# LVDT_Driver.net
KiCad netlist of a schematic drawn in Altium Designer
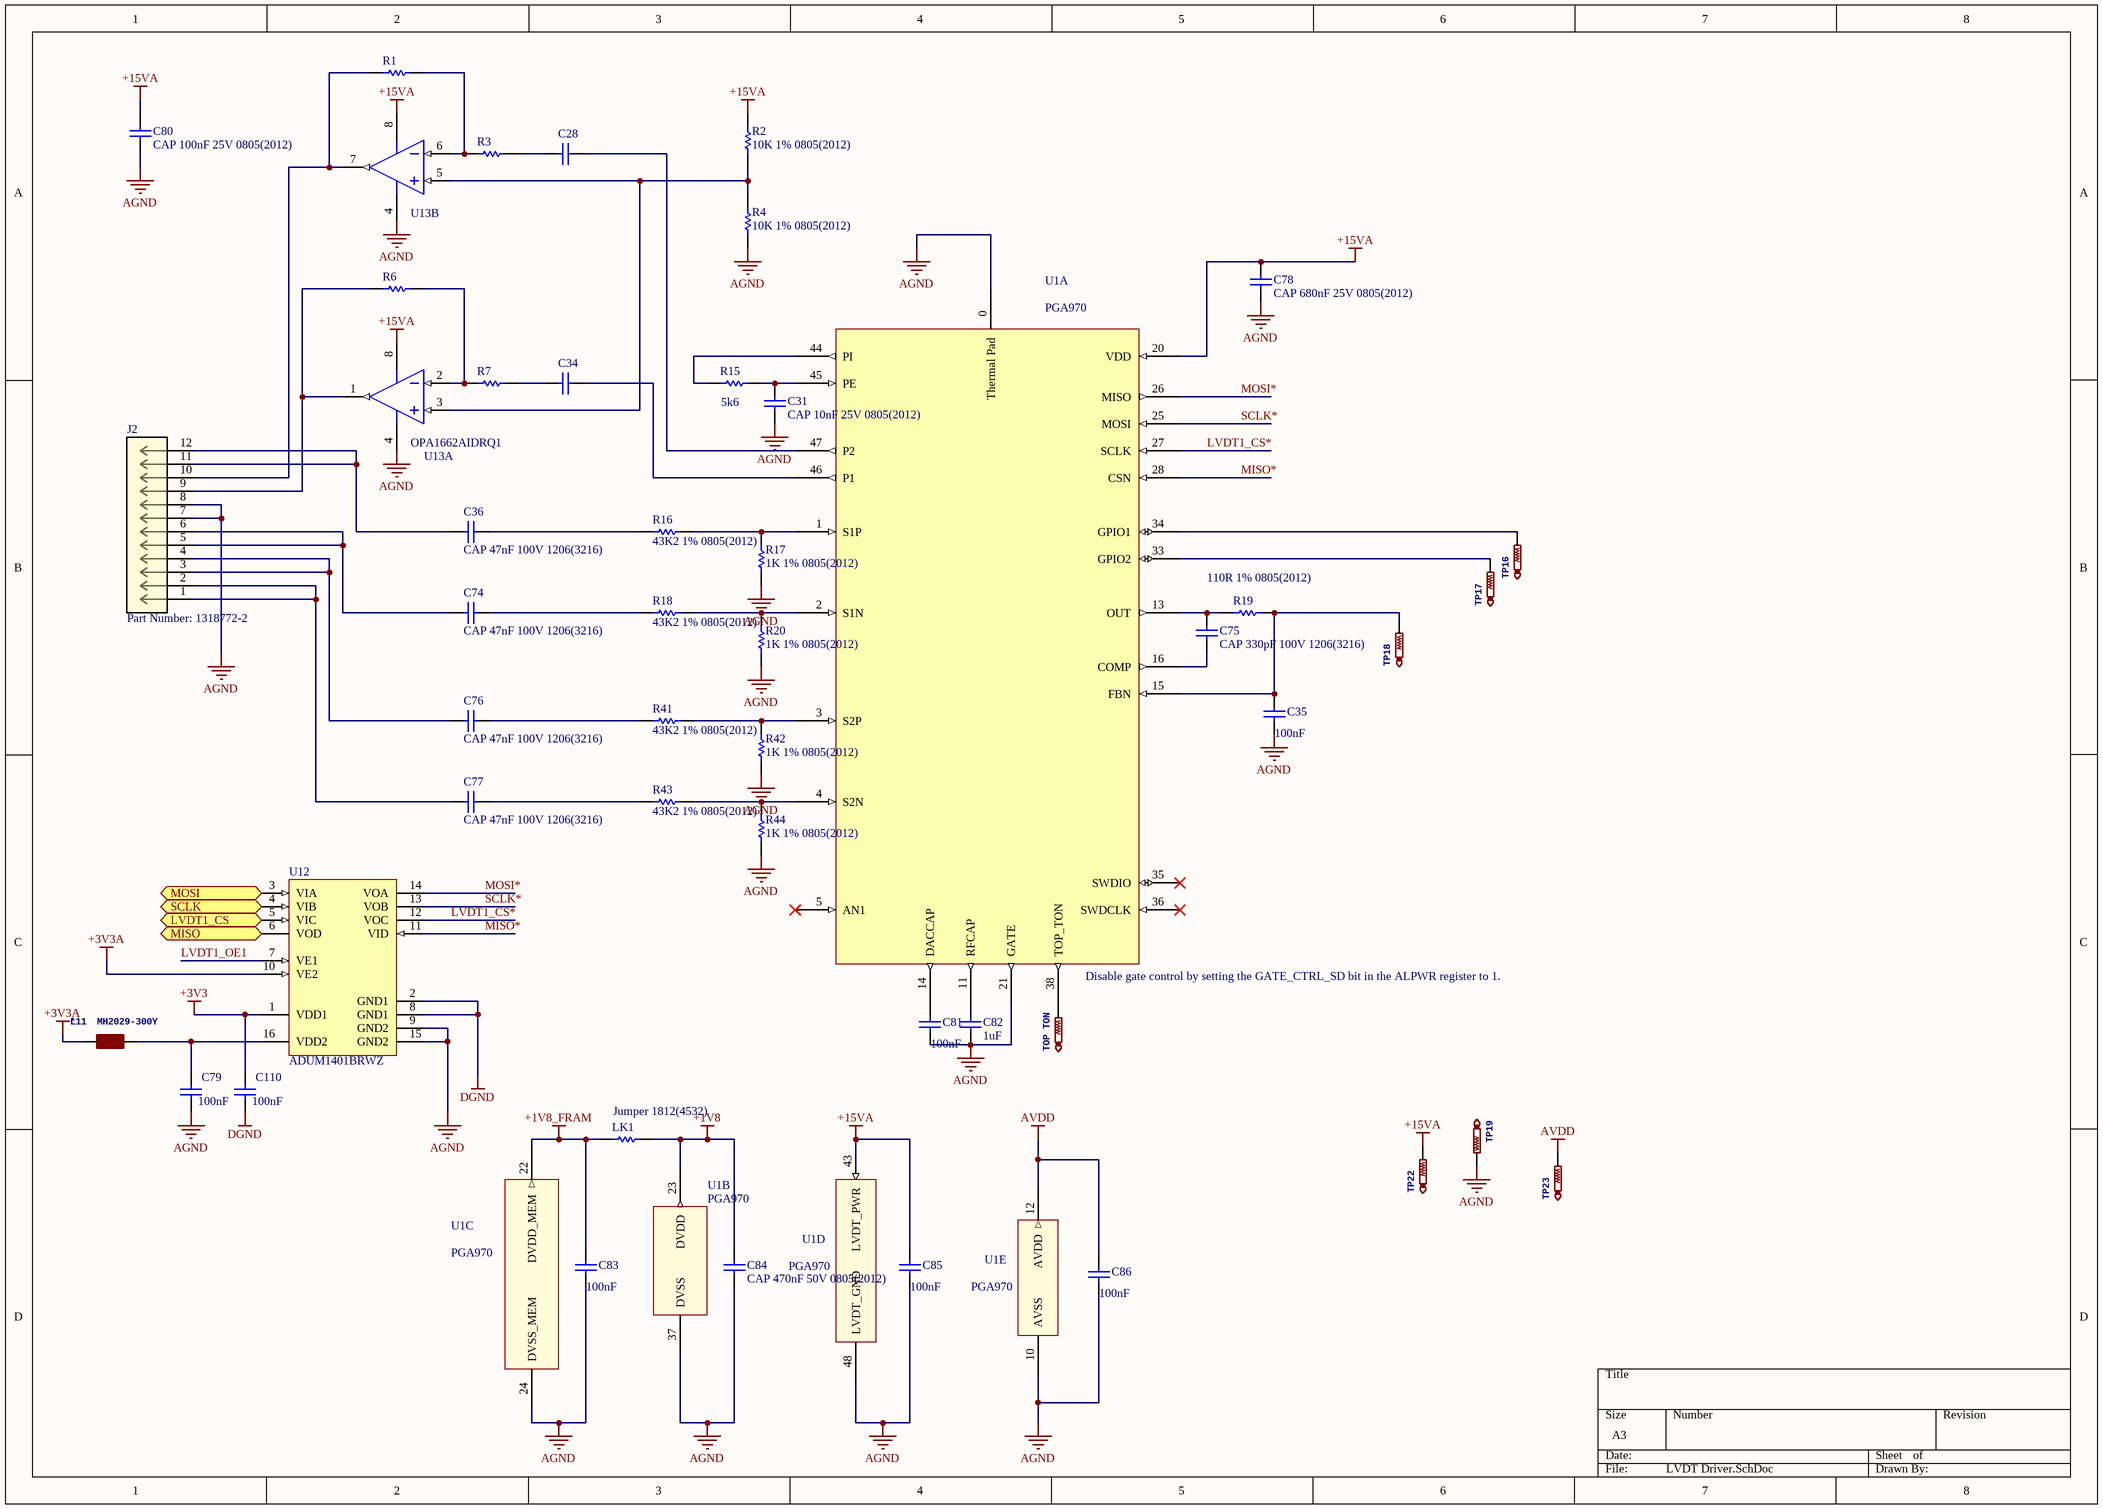
[diagram p0: LVDT Driver.SchDoc]

(export (version "E")
  (design (tool "Eeschema 10.0.6"))
  (components
    (comp (ref "C28")
      (value "C1206C474K5RACTU")
      (footprint "CAPC3216X100X50LL20T25")
      (description "Chip Capacitor, 470 nF, +/- 10%, 50 V, -55 to 125 degC, 1206 (3216 Metric), RoHS, Tape and Reel")
      (fields (field (name "MANUFACTURER") "Kemet") (field (name "TOLERANCE") "10%"))
      (libsource (lib "Altium Content Vault") (part "CAP-NP-2"))
    )
    (comp (ref "C31")
      (value "CAP 10nF 25V 0805(2012)")
      (footprint "CAPC0805(2012)75_L")
      (description "CAP 10nF 25V ±5% 0805 (2012 Metric) Thickness 0.75mm SMD")
      (fields (field (name "TOLERANCE") "Â±5%"))
      (libsource (lib "Altium Content Vault") (part "CAP"))
    )
    (comp (ref "C34")
      (value "C1206C474K5RACTU")
      (footprint "CAPC3216X100X50LL20T25")
      (description "Chip Capacitor, 470 nF, +/- 10%, 50 V, -55 to 125 degC, 1206 (3216 Metric), RoHS, Tape and Reel")
      (fields (field (name "MANUFACTURER") "Kemet") (field (name "TOLERANCE") "10%"))
      (libsource (lib "Altium Content Vault") (part "CAP-NP-2"))
    )
    (comp (ref "C35")
      (value "100nF")
      (footprint "CAPC0805(2012)75_N")
      (description "CAP 100nF 25V -20% to +80% 0805 (2012 Metric) Thickness 0.75mm SMD")
      (fields (field (name "TOLERANCE") "-20% to +80%"))
      (libsource (lib "Altium Content Vault") (part "CMP-1036-04415-1"))
    )
    (comp (ref "C36")
      (value "CAP 47nF 100V 1206(3216)")
      (footprint "CAPC1206(3216)100_L")
      (description "CAP 47nF 100V ±20% 1206 (3216 Metric) Thickness 1mm SMD")
      (fields (field (name "TOLERANCE") "Â±20%"))
      (libsource (lib "Altium Content Vault") (part "CAP"))
    )
    (comp (ref "C74")
      (value "CAP 47nF 100V 1206(3216)")
      (footprint "CAPC1206(3216)100_L")
      (description "CAP 47nF 100V ±20% 1206 (3216 Metric) Thickness 1mm SMD")
      (fields (field (name "TOLERANCE") "Â±20%"))
      (libsource (lib "Altium Content Vault") (part "CAP"))
    )
    (comp (ref "C75")
      (value "CAP 330pF 100V 1206(3216)")
      (footprint "CAPC1206(3216)170_L")
      (description "CAP 330pF 100V ±1% 1206 (3216 Metric) Thickness 1.7mm SMD")
      (fields (field (name "TOLERANCE") "Â±1%"))
      (libsource (lib "Altium Content Vault") (part "CAP"))
    )
    (comp (ref "C76")
      (value "CAP 47nF 100V 1206(3216)")
      (footprint "CAPC1206(3216)100_L")
      (description "CAP 47nF 100V ±20% 1206 (3216 Metric) Thickness 1mm SMD")
      (fields (field (name "TOLERANCE") "Â±20%"))
      (libsource (lib "Altium Content Vault") (part "CAP"))
    )
    (comp (ref "C77")
      (value "CAP 47nF 100V 1206(3216)")
      (footprint "CAPC1206(3216)100_L")
      (description "CAP 47nF 100V ±20% 1206 (3216 Metric) Thickness 1mm SMD")
      (fields (field (name "TOLERANCE") "Â±20%"))
      (libsource (lib "Altium Content Vault") (part "CAP"))
    )
    (comp (ref "C78")
      (value "CAP 680nF 25V 0805(2012)")
      (footprint "CAPC0805(2012)100_N")
      (description "CAP 680nF 25V ±10% 0805 (2012 Metric) Thickness 1mm SMD")
      (fields (field (name "TOLERANCE") "Â±10%"))
      (libsource (lib "Altium Content Vault") (part "CAP"))
    )
    (comp (ref "C79")
      (value "100nF")
      (footprint "CAPC0603(1608)100_N")
      (description "CAP 100nF 25V ±5% 0603 (1608 Metric) Thickness 1mm SMD")
      (fields (field (name "TOLERANCE") "Â±5%") (field (name "Comment") "CAP 100nF 25V 0603(1608)"))
      (libsource (lib "Altium Content Vault") (part "CMP-1035-02587-1"))
    )
    (comp (ref "C80")
      (value "CAP 100nF 25V 0805(2012)")
      (footprint "CAPC0805(2012)75_N")
      (description "CAP 100nF 25V -20% to +80% 0805 (2012 Metric) Thickness 0.75mm SMD")
      (fields (field (name "TOLERANCE") "-20% to +80%"))
      (libsource (lib "Altium Content Vault") (part "CAP"))
    )
    (comp (ref "C81")
      (value "100nF")
      (footprint "CAPC0805(2012)75_N")
      (description "CAP 100nF 25V -20% to +80% 0805 (2012 Metric) Thickness 0.75mm SMD")
      (fields (field (name "TOLERANCE") "-20% to +80%"))
      (libsource (lib "Altium Content Vault") (part "CMP-1036-04415-1"))
    )
    (comp (ref "C82")
      (value "1uF")
      (footprint "CAPC2220(5750)230_L")
      (description "CAP 4.7uF 50V ±10% 2220 (5750 Metric) Thickness 2.2mm SMD")
      (fields (field (name "TOLERANCE") "Â±10%") (field (name "Comment") "CAP 4.7uF 50V 2220(5750)"))
      (libsource (lib "Altium Content Vault") (part "CMP-1042-00755-1"))
    )
    (comp (ref "C83")
      (value "100nF")
      (footprint "CAPC0805(2012)75_N")
      (description "CAP 100nF 25V -20% to +80% 0805 (2012 Metric) Thickness 0.75mm SMD")
      (fields (field (name "TOLERANCE") "-20% to +80%"))
      (libsource (lib "Altium Content Vault") (part "CMP-1036-04415-1"))
    )
    (comp (ref "C84")
      (value "CAP 470nF 50V 0805(2012)")
      (footprint "CAPC0805(2012)145_M")
      (description "CAP 470nF 50V ±10% 0805 (2012 Metric) Thickness 1.45mm SMD")
      (fields (field (name "TOLERANCE") "Â±10%"))
      (libsource (lib "Altium Content Vault") (part "CAP"))
    )
    (comp (ref "C85")
      (value "100nF")
      (footprint "CAPC0805(2012)75_N")
      (description "CAP 100nF 25V -20% to +80% 0805 (2012 Metric) Thickness 0.75mm SMD")
      (fields (field (name "TOLERANCE") "-20% to +80%"))
      (libsource (lib "Altium Content Vault") (part "CMP-1036-04415-1"))
    )
    (comp (ref "C86")
      (value "100nF")
      (footprint "CAPC0805(2012)75_N")
      (description "CAP 100nF 25V -20% to +80% 0805 (2012 Metric) Thickness 0.75mm SMD")
      (fields (field (name "TOLERANCE") "-20% to +80%"))
      (libsource (lib "Altium Content Vault") (part "CMP-1036-04415-1"))
    )
    (comp (ref "C110")
      (value "100nF")
      (footprint "CAPC0603(1608)100_N")
      (description "CAP 100nF 25V ±5% 0603 (1608 Metric) Thickness 1mm SMD")
      (fields (field (name "TOLERANCE") "Â±5%") (field (name "Comment") "CAP 100nF 25V 0603(1608)"))
      (libsource (lib "Altium Content Vault") (part "CMP-1035-02587-1"))
    )
    (comp (ref "J2")
      (value "Part Number: 1318772-2")
      (footprint "CONN12_1318772")
      (description "025 CAP HSG ASSY 12P")
      (fields
        (field (name "MANUFACTURER_PART_NUMBER") "1318772-2")
        (field (name "COPYRIGHT") "Copyright (C) 2016 Accelerated Designs. All rights reserved")
      )
      (libsource (lib "2019-12-12_01-42-35") (part "1318772-2"))
    )
    (comp (ref "L11")
      (value "MH2029-300Y")
      (footprint "0805")
      (fields (field (name "NAME") "*"))
      (libsource (lib "wuerth-elektronik") (part "WE-CBF_0805"))
    )
    (comp (ref "LK1")
      (value "Jumper 1812(4532)")
      (footprint "RESC1812(4532)_M")
      (description "Jumper 1812 (4532 Metric)")
      (fields (field (name "TOLERANCE") "None"))
      (libsource (lib "Altium Content Vault") (part "RES"))
    )
    (comp (ref "R1")
      (value "510K 1% 0805(2012)")
      (footprint "RESC0805(2012)_L")
      (description "510K 0.125W 1% 0805 (2012 Metric)  SMD")
      (fields (field (name "POWER") "0.125 W") (field (name "TOLERANCE") "1 %"))
      (libsource (lib "Altium Content Vault") (part "RES"))
    )
    (comp (ref "R2")
      (value "10K 1% 0805(2012)")
      (footprint "RESC0805(2012)_M")
      (description "10K 0.125W 1% 0805 (2012 Metric)  SMD")
      (fields (field (name "TOLERANCE") "1 %") (field (name "POWER") "0.125 W"))
      (libsource (lib "Altium Content Vault") (part "RES"))
    )
    (comp (ref "R3")
      (value "31K6 1% 0805(2012)")
      (footprint "RESC0805(2012)_N")
      (description "31K6 0.125W 1% 0805 (2012 Metric)  SMD")
      (fields (field (name "TOLERANCE") "1 %") (field (name "POWER") "0.125 W"))
      (libsource (lib "Altium Content Vault") (part "RES"))
    )
    (comp (ref "R4")
      (value "10K 1% 0805(2012)")
      (footprint "RESC0805(2012)_M")
      (description "10K 0.125W 1% 0805 (2012 Metric)  SMD")
      (fields (field (name "TOLERANCE") "1 %") (field (name "POWER") "0.125 W"))
      (libsource (lib "Altium Content Vault") (part "RES"))
    )
    (comp (ref "R6")
      (value "510K 1% 0805(2012)")
      (footprint "RESC0805(2012)_L")
      (description "510K 0.125W 1% 0805 (2012 Metric)  SMD")
      (fields (field (name "POWER") "0.125 W") (field (name "TOLERANCE") "1 %"))
      (libsource (lib "Altium Content Vault") (part "RES"))
    )
    (comp (ref "R7")
      (value "31K6 1% 0805(2012)")
      (footprint "RESC0805(2012)_N")
      (description "31K6 0.125W 1% 0805 (2012 Metric)  SMD")
      (fields (field (name "TOLERANCE") "1 %") (field (name "POWER") "0.125 W"))
      (libsource (lib "Altium Content Vault") (part "RES"))
    )
    (comp (ref "R15")
      (value "5k6")
      (footprint "RESC0805(2012)_L")
      (description "5K6 0.125W 1% 0805 (2012 Metric)  SMD")
      (fields (field (name "POWER") "0.125 W") (field (name "TOLERANCE") "1 %"))
      (libsource (lib "Altium Content Vault") (part "CMP-1013-00595-1"))
    )
    (comp (ref "R16")
      (value "43K2 1% 0805(2012)")
      (footprint "RESC0805(2012)_L")
      (description "43K2 0.125W 1% 0805 (2012 Metric)  SMD")
      (fields (field (name "POWER") "0.125 W") (field (name "TOLERANCE") "1 %"))
      (libsource (lib "Altium Content Vault") (part "RES"))
    )
    (comp (ref "R17")
      (value "1K 1% 0805(2012)")
      (footprint "RESC0805(2012)_M")
      (description "1K 0.125W 1% 0805 (2012 Metric)  SMD")
      (fields (field (name "TOLERANCE") "1 %") (field (name "POWER") "0.125 W"))
      (libsource (lib "Altium Content Vault") (part "RES"))
    )
    (comp (ref "R18")
      (value "43K2 1% 0805(2012)")
      (footprint "RESC0805(2012)_L")
      (description "43K2 0.125W 1% 0805 (2012 Metric)  SMD")
      (fields (field (name "POWER") "0.125 W") (field (name "TOLERANCE") "1 %"))
      (libsource (lib "Altium Content Vault") (part "RES"))
    )
    (comp (ref "R19")
      (value "110R 1% 0805(2012)")
      (footprint "RESC0805(2012)_L")
      (description "110R 0.125W 1% 0805 (2012 Metric)  SMD")
      (fields (field (name "TOLERANCE") "1 %") (field (name "POWER") "0.125 W"))
      (libsource (lib "Altium Content Vault") (part "RES"))
    )
    (comp (ref "R20")
      (value "1K 1% 0805(2012)")
      (footprint "RESC0805(2012)_M")
      (description "1K 0.125W 1% 0805 (2012 Metric)  SMD")
      (fields (field (name "TOLERANCE") "1 %") (field (name "POWER") "0.125 W"))
      (libsource (lib "Altium Content Vault") (part "RES"))
    )
    (comp (ref "R41")
      (value "43K2 1% 0805(2012)")
      (footprint "RESC0805(2012)_L")
      (description "43K2 0.125W 1% 0805 (2012 Metric)  SMD")
      (fields (field (name "POWER") "0.125 W") (field (name "TOLERANCE") "1 %"))
      (libsource (lib "Altium Content Vault") (part "RES"))
    )
    (comp (ref "R42")
      (value "1K 1% 0805(2012)")
      (footprint "RESC0805(2012)_M")
      (description "1K 0.125W 1% 0805 (2012 Metric)  SMD")
      (fields (field (name "TOLERANCE") "1 %") (field (name "POWER") "0.125 W"))
      (libsource (lib "Altium Content Vault") (part "RES"))
    )
    (comp (ref "R43")
      (value "43K2 1% 0805(2012)")
      (footprint "RESC0805(2012)_L")
      (description "43K2 0.125W 1% 0805 (2012 Metric)  SMD")
      (fields (field (name "POWER") "0.125 W") (field (name "TOLERANCE") "1 %"))
      (libsource (lib "Altium Content Vault") (part "RES"))
    )
    (comp (ref "R44")
      (value "1K 1% 0805(2012)")
      (footprint "RESC0805(2012)_M")
      (description "1K 0.125W 1% 0805 (2012 Metric)  SMD")
      (fields (field (name "TOLERANCE") "1 %") (field (name "POWER") "0.125 W"))
      (libsource (lib "Altium Content Vault") (part "RES"))
    )
    (comp (ref "TOP TON")
      (value "PTR1PAD1-13")
      (footprint "P1-13")
      (description "TEST PIN")
      (libsource (lib "testpad") (part "PTR1PAD1-13"))
    )
    (comp (ref "TP16")
      (value "PTR1PAD1-13")
      (footprint "P1-13")
      (description "TEST PIN")
      (libsource (lib "testpad") (part "PTR1PAD1-13"))
    )
    (comp (ref "TP17")
      (value "PTR1PAD1-13")
      (footprint "P1-13")
      (description "TEST PIN")
      (libsource (lib "testpad") (part "PTR1PAD1-13"))
    )
    (comp (ref "TP18")
      (value "PTR1PAD1-13")
      (footprint "P1-13")
      (description "TEST PIN")
      (libsource (lib "testpad") (part "PTR1PAD1-13"))
    )
    (comp (ref "TP19")
      (value "PTR1PAD1-13")
      (footprint "P1-13")
      (description "TEST PIN")
      (libsource (lib "") (part "PTR1PAD1-13_1"))
    )
    (comp (ref "TP22")
      (value "PTR1PAD1-13")
      (footprint "P1-13")
      (description "TEST PIN")
      (libsource (lib "testpad") (part "PTR1PAD1-13"))
    )
    (comp (ref "TP23")
      (value "PTR1PAD1-13")
      (footprint "P1-13")
      (description "TEST PIN")
      (libsource (lib "testpad") (part "PTR1PAD1-13"))
    )
    (comp (ref "U1")
      (value "PGA970")
      (footprint "PHP0048A_L")
      (libsource (lib "Length Bar Comparator") (part "PGA970"))
    )
    (comp (ref "U12")
      (value "ADUM1401BRWZ")
      (footprint "ADI-RW-16_M")
      (fields (field (name "MANUFACTURER") "Analog Devices"))
      (libsource (lib "Altium Content Vault") (part "ADI-ADUMX4X1-16"))
    )
    (comp (ref "U13")
      (value "OPA1662AIDRQ1")
      (footprint "D0008A_L")
      (fields (field (name "MANUFACTURER") "Texas Instruments"))
      (libsource (lib "Altium Content Vault") (part "CMP-0271-00139-3"))
    )
  )
  (nets
    (net (code "1") (name "+1V8") (class "Default")
      (node (ref "C84") (pin "2") (pinfunction "2_2") (pintype "passive"))
      (node (ref "LK1") (pin "2") (pinfunction "2_2") (pintype "passive"))
      (node (ref "U1") (pin "23") (pinfunction "DVDD_23") (pintype "output"))
    )
    (net (code "2") (name "+1V8_FRAM") (class "Default")
      (node (ref "C83") (pin "2") (pinfunction "2_2") (pintype "passive"))
      (node (ref "LK1") (pin "1") (pinfunction "1_1") (pintype "passive"))
      (node (ref "U1") (pin "22") (pinfunction "DVDD_MEM_22") (pintype "output"))
    )
    (net (code "3") (name "+3V3") (class "Default")
      (node (ref "C110") (pin "1") (pinfunction "1_1") (pintype "passive"))
      (node (ref "U12") (pin "1") (pinfunction "VDD1_1") (pintype "power_in"))
    )
    (net (code "4") (name "+3V3A") (class "Default")
      (node (ref "L11") (pin "1") (pinfunction "1_1") (pintype "passive"))
      (node (ref "U12") (pin "10") (pinfunction "VE2_10") (pintype "input"))
    )
    (net (code "5") (name "+15VA") (class "Default")
      (node (ref "C78") (pin "2") (pinfunction "2_2") (pintype "passive"))
      (node (ref "C80") (pin "2") (pinfunction "2_2") (pintype "passive"))
      (node (ref "C85") (pin "2") (pinfunction "2_2") (pintype "passive"))
      (node (ref "R2") (pin "2") (pinfunction "2_2") (pintype "passive"))
      (node (ref "TP22") (pin "TP") (pinfunction "TP_TP") (pintype "passive"))
      (node (ref "U1") (pin "20") (pinfunction "VDD_20") (pintype "input"))
      (node (ref "U1") (pin "43") (pinfunction "LVDT_PWR_43") (pintype "input"))
      (node (ref "U13") (pin "8") (pinfunction "V+_8") (pintype "power_in"))
    )
    (net (code "6") (name "/LVDT1_CS") (class "Default")
      (node (ref "U12") (pin "5") (pinfunction "VIC_5") (pintype "input"))
    )
    (net (code "7") (name "/LVDT1_CS*") (class "Default")
      (node (ref "U1") (pin "27") (pinfunction "SCLK_27") (pintype "input"))
      (node (ref "U12") (pin "12") (pinfunction "VOC_12") (pintype "tri_state"))
    )
    (net (code "8") (name "/LVDT1_OE1") (class "Default")
      (node (ref "U12") (pin "7") (pinfunction "VE1_7") (pintype "input"))
    )
    (net (code "9") (name "/MISO") (class "Default")
      (node (ref "U12") (pin "6") (pinfunction "VOD_6") (pintype "tri_state"))
    )
    (net (code "10") (name "/MISO*") (class "Default")
      (node (ref "U1") (pin "28") (pinfunction "CSN_28") (pintype "input"))
      (node (ref "U12") (pin "11") (pinfunction "VID_11") (pintype "input"))
    )
    (net (code "11") (name "/MOSI") (class "Default")
      (node (ref "U12") (pin "3") (pinfunction "VIA_3") (pintype "input"))
    )
    (net (code "12") (name "/MOSI*") (class "Default")
      (node (ref "U1") (pin "26") (pinfunction "MISO_26") (pintype "output"))
      (node (ref "U12") (pin "14") (pinfunction "VOA_14") (pintype "tri_state"))
    )
    (net (code "13") (name "/SCLK") (class "Default")
      (node (ref "U12") (pin "4") (pinfunction "VIB_4") (pintype "input"))
    )
    (net (code "14") (name "/SCLK*") (class "Default")
      (node (ref "U1") (pin "25") (pinfunction "MOSI_25") (pintype "input"))
      (node (ref "U12") (pin "13") (pinfunction "VOB_13") (pintype "tri_state"))
    )
    (net (code "15") (name "AGND") (class "Default")
      (node (ref "C31") (pin "1") (pinfunction "1_1") (pintype "passive"))
      (node (ref "C35") (pin "1") (pinfunction "1_1") (pintype "passive"))
      (node (ref "C78") (pin "1") (pinfunction "1_1") (pintype "passive"))
      (node (ref "C79") (pin "2") (pinfunction "2_2") (pintype "passive"))
      (node (ref "C80") (pin "1") (pinfunction "1_1") (pintype "passive"))
      (node (ref "C81") (pin "1") (pinfunction "1_1") (pintype "passive"))
      (node (ref "C82") (pin "1") (pinfunction "1_1") (pintype "passive"))
      (node (ref "C83") (pin "1") (pinfunction "1_1") (pintype "passive"))
      (node (ref "C84") (pin "1") (pinfunction "1_1") (pintype "passive"))
      (node (ref "C85") (pin "1") (pinfunction "1_1") (pintype "passive"))
      (node (ref "C86") (pin "1") (pinfunction "1_1") (pintype "passive"))
      (node (ref "J2") (pin "7") (pinfunction "7_7") (pintype "passive"))
      (node (ref "J2") (pin "8") (pinfunction "8_8") (pintype "passive"))
      (node (ref "R17") (pin "1") (pinfunction "1_1") (pintype "passive"))
      (node (ref "R20") (pin "1") (pinfunction "1_1") (pintype "passive"))
      (node (ref "R4") (pin "1") (pinfunction "1_1") (pintype "passive"))
      (node (ref "R42") (pin "1") (pinfunction "1_1") (pintype "passive"))
      (node (ref "R44") (pin "1") (pinfunction "1_1") (pintype "passive"))
      (node (ref "TP19") (pin "TP") (pinfunction "TP_TP") (pintype "passive"))
      (node (ref "U1") (pin "0") (pinfunction "Thermal_Pad_0") (pintype "passive"))
      (node (ref "U1") (pin "10") (pinfunction "AVSS_10") (pintype "power_in"))
      (node (ref "U1") (pin "21") (pinfunction "GATE_21") (pintype "output"))
      (node (ref "U1") (pin "24") (pinfunction "DVSS_MEM_24") (pintype "power_in"))
      (node (ref "U1") (pin "37") (pinfunction "DVSS_37") (pintype "power_in"))
      (node (ref "U1") (pin "48") (pinfunction "LVDT_GND_48") (pintype "power_in"))
      (node (ref "U12") (pin "15") (pinfunction "GND2_15") (pintype "power_in"))
      (node (ref "U12") (pin "9") (pinfunction "GND2_9") (pintype "power_in"))
      (node (ref "U13") (pin "4") (pinfunction "V-_4") (pintype "power_in"))
    )
    (net (code "16") (name "AVDD") (class "Default")
      (node (ref "C86") (pin "2") (pinfunction "2_2") (pintype "passive"))
      (node (ref "TP23") (pin "TP") (pinfunction "TP_TP") (pintype "passive"))
      (node (ref "U1") (pin "12") (pinfunction "AVDD_12") (pintype "output"))
    )
    (net (code "17") (name "DGND") (class "Default")
      (node (ref "C110") (pin "2") (pinfunction "2_2") (pintype "passive"))
      (node (ref "U12") (pin "2") (pinfunction "GND1_2") (pintype "power_in"))
      (node (ref "U12") (pin "8") (pinfunction "GND1_8") (pintype "power_in"))
    )
    (net (code "18") (name "Net-(C28-Pad1)") (class "Default")
      (node (ref "C28") (pin "1") (pinfunction "1_1") (pintype "passive"))
      (node (ref "R3") (pin "2") (pinfunction "2_2") (pintype "passive"))
    )
    (net (code "19") (name "Net-(C34-Pad1)") (class "Default")
      (node (ref "C34") (pin "1") (pinfunction "1_1") (pintype "passive"))
      (node (ref "R7") (pin "2") (pinfunction "2_2") (pintype "passive"))
    )
    (net (code "20") (name "Net-(C36-Pad1)") (class "Default")
      (node (ref "C36") (pin "1") (pinfunction "1_1") (pintype "passive"))
      (node (ref "J2") (pin "11") (pinfunction "11_11") (pintype "passive"))
      (node (ref "J2") (pin "12") (pinfunction "12_12") (pintype "passive"))
    )
    (net (code "21") (name "Net-(C36-Pad2)") (class "Default")
      (node (ref "C36") (pin "2") (pinfunction "2_2") (pintype "passive"))
      (node (ref "R16") (pin "1") (pinfunction "1_1") (pintype "passive"))
    )
    (net (code "22") (name "Net-(C74-Pad1)") (class "Default")
      (node (ref "C74") (pin "1") (pinfunction "1_1") (pintype "passive"))
      (node (ref "J2") (pin "5") (pinfunction "5_5") (pintype "passive"))
      (node (ref "J2") (pin "6") (pinfunction "6_6") (pintype "passive"))
    )
    (net (code "23") (name "Net-(C74-Pad2)") (class "Default")
      (node (ref "C74") (pin "2") (pinfunction "2_2") (pintype "passive"))
      (node (ref "R18") (pin "1") (pinfunction "1_1") (pintype "passive"))
    )
    (net (code "24") (name "Net-(C76-Pad1)") (class "Default")
      (node (ref "C76") (pin "1") (pinfunction "1_1") (pintype "passive"))
      (node (ref "J2") (pin "3") (pinfunction "3_3") (pintype "passive"))
      (node (ref "J2") (pin "4") (pinfunction "4_4") (pintype "passive"))
    )
    (net (code "25") (name "Net-(C76-Pad2)") (class "Default")
      (node (ref "C76") (pin "2") (pinfunction "2_2") (pintype "passive"))
      (node (ref "R41") (pin "1") (pinfunction "1_1") (pintype "passive"))
    )
    (net (code "26") (name "Net-(C77-Pad1)") (class "Default")
      (node (ref "C77") (pin "1") (pinfunction "1_1") (pintype "passive"))
      (node (ref "J2") (pin "1") (pinfunction "1_1") (pintype "passive"))
      (node (ref "J2") (pin "2") (pinfunction "2_2") (pintype "passive"))
    )
    (net (code "27") (name "Net-(C77-Pad2)") (class "Default")
      (node (ref "C77") (pin "2") (pinfunction "2_2") (pintype "passive"))
      (node (ref "R43") (pin "1") (pinfunction "1_1") (pintype "passive"))
    )
    (net (code "28") (name "Net-(U1A-COMP)") (class "Default")
      (node (ref "C75") (pin "1") (pinfunction "1_1") (pintype "passive"))
      (node (ref "U1") (pin "16") (pinfunction "COMP_16") (pintype "output"))
    )
    (net (code "29") (name "Net-(U1A-DACCAP)") (class "Default")
      (node (ref "C81") (pin "2") (pinfunction "2_2") (pintype "passive"))
      (node (ref "U1") (pin "14") (pinfunction "DACCAP_14") (pintype "output"))
    )
    (net (code "30") (name "Net-(U1A-FBN)") (class "Default")
      (node (ref "C35") (pin "2") (pinfunction "2_2") (pintype "passive"))
      (node (ref "R19") (pin "2") (pinfunction "2_2") (pintype "passive"))
      (node (ref "TP18") (pin "TP") (pinfunction "TP_TP") (pintype "passive"))
      (node (ref "U1") (pin "15") (pinfunction "FBN_15") (pintype "input"))
    )
    (net (code "31") (name "Net-(U1A-GPIO1)") (class "Default")
      (node (ref "TP16") (pin "TP") (pinfunction "TP_TP") (pintype "passive"))
      (node (ref "U1") (pin "34") (pinfunction "GPIO1_34") (pintype "bidirectional"))
    )
    (net (code "32") (name "Net-(U1A-GPIO2)") (class "Default")
      (node (ref "TP17") (pin "TP") (pinfunction "TP_TP") (pintype "passive"))
      (node (ref "U1") (pin "33") (pinfunction "GPIO2_33") (pintype "bidirectional"))
    )
    (net (code "33") (name "Net-(U1A-OUT)") (class "Default")
      (node (ref "C75") (pin "2") (pinfunction "2_2") (pintype "passive"))
      (node (ref "R19") (pin "1") (pinfunction "1_1") (pintype "passive"))
      (node (ref "U1") (pin "13") (pinfunction "OUT_13") (pintype "output"))
    )
    (net (code "34") (name "Net-(U1A-P1)") (class "Default")
      (node (ref "C34") (pin "2") (pinfunction "2_2") (pintype "passive"))
      (node (ref "U1") (pin "46") (pinfunction "P1_46") (pintype "output"))
    )
    (net (code "35") (name "Net-(U1A-P2)") (class "Default")
      (node (ref "C28") (pin "2") (pinfunction "2_2") (pintype "passive"))
      (node (ref "U1") (pin "47") (pinfunction "P2_47") (pintype "output"))
    )
    (net (code "36") (name "Net-(U1A-PE)") (class "Default")
      (node (ref "C31") (pin "2") (pinfunction "2_2") (pintype "passive"))
      (node (ref "R15") (pin "2") (pinfunction "2_2") (pintype "passive"))
      (node (ref "U1") (pin "45") (pinfunction "PE_45") (pintype "input"))
    )
    (net (code "37") (name "Net-(U1A-PI)") (class "Default")
      (node (ref "R15") (pin "1") (pinfunction "1_1") (pintype "passive"))
      (node (ref "U1") (pin "44") (pinfunction "PI_44") (pintype "output"))
    )
    (net (code "38") (name "Net-(U1A-RFCAP)") (class "Default")
      (node (ref "C82") (pin "2") (pinfunction "2_2") (pintype "passive"))
      (node (ref "U1") (pin "11") (pinfunction "RFCAP_11") (pintype "output"))
    )
    (net (code "39") (name "Net-(U1A-S1N)") (class "Default")
      (node (ref "R18") (pin "2") (pinfunction "2_2") (pintype "passive"))
      (node (ref "R20") (pin "2") (pinfunction "2_2") (pintype "passive"))
      (node (ref "U1") (pin "2") (pinfunction "S1N_2") (pintype "input"))
    )
    (net (code "40") (name "Net-(U1A-S1P)") (class "Default")
      (node (ref "R16") (pin "2") (pinfunction "2_2") (pintype "passive"))
      (node (ref "R17") (pin "2") (pinfunction "2_2") (pintype "passive"))
      (node (ref "U1") (pin "1") (pinfunction "S1P_1") (pintype "input"))
    )
    (net (code "41") (name "Net-(U1A-S2N)") (class "Default")
      (node (ref "R43") (pin "2") (pinfunction "2_2") (pintype "passive"))
      (node (ref "R44") (pin "2") (pinfunction "2_2") (pintype "passive"))
      (node (ref "U1") (pin "4") (pinfunction "S2N_4") (pintype "input"))
    )
    (net (code "42") (name "Net-(U1A-S2P)") (class "Default")
      (node (ref "R41") (pin "2") (pinfunction "2_2") (pintype "passive"))
      (node (ref "R42") (pin "2") (pinfunction "2_2") (pintype "passive"))
      (node (ref "U1") (pin "3") (pinfunction "S2P_3") (pintype "input"))
    )
    (net (code "43") (name "Net-(U1A-TOP_TON)") (class "Default")
      (node (ref "TOP TON") (pin "TP") (pinfunction "TP_TP") (pintype "passive"))
      (node (ref "U1") (pin "38") (pinfunction "TOP_TON_38") (pintype "output"))
    )
    (net (code "44") (name "Net-(U12-VDD2)") (class "Default")
      (node (ref "C79") (pin "1") (pinfunction "1_1") (pintype "passive"))
      (node (ref "L11") (pin "2") (pinfunction "2_2") (pintype "passive"))
      (node (ref "U12") (pin "16") (pinfunction "VDD2_16") (pintype "power_in"))
    )
    (net (code "45") (name "Net-(U13A-IN_A+)") (class "Default")
      (node (ref "R2") (pin "1") (pinfunction "1_1") (pintype "passive"))
      (node (ref "R4") (pin "2") (pinfunction "2_2") (pintype "passive"))
      (node (ref "U13") (pin "3") (pinfunction "IN_A+_3") (pintype "input"))
      (node (ref "U13") (pin "5") (pinfunction "IN_B+_5") (pintype "input"))
    )
    (net (code "46") (name "Net-(U13A-IN_A-)") (class "Default")
      (node (ref "R6") (pin "2") (pinfunction "2_2") (pintype "passive"))
      (node (ref "R7") (pin "1") (pinfunction "1_1") (pintype "passive"))
      (node (ref "U13") (pin "2") (pinfunction "IN_A-_2") (pintype "input"))
    )
    (net (code "47") (name "Net-(U13A-OUT_A)") (class "Default")
      (node (ref "J2") (pin "9") (pinfunction "9_9") (pintype "passive"))
      (node (ref "R6") (pin "1") (pinfunction "1_1") (pintype "passive"))
      (node (ref "U13") (pin "1") (pinfunction "OUT_A_1") (pintype "output"))
    )
    (net (code "48") (name "Net-(U13B-IN_B-)") (class "Default")
      (node (ref "R1") (pin "2") (pinfunction "2_2") (pintype "passive"))
      (node (ref "R3") (pin "1") (pinfunction "1_1") (pintype "passive"))
      (node (ref "U13") (pin "6") (pinfunction "IN_B-_6") (pintype "input"))
    )
    (net (code "49") (name "Net-(U13B-OUT_B)") (class "Default")
      (node (ref "J2") (pin "10") (pinfunction "10_10") (pintype "passive"))
      (node (ref "R1") (pin "1") (pinfunction "1_1") (pintype "passive"))
      (node (ref "U13") (pin "7") (pinfunction "OUT_B_7") (pintype "output"))
    )
    (net (code "50") (name "unconnected-(U1A-AN1-Pad5)") (class "Default")
      (node (ref "U1") (pin "5") (pinfunction "AN1_5") (pintype "input+no_connect"))
    )
    (net (code "51") (name "unconnected-(U1A-SWDCLK-Pad36)") (class "Default")
      (node (ref "U1") (pin "36") (pinfunction "SWDCLK_36") (pintype "input+no_connect"))
    )
    (net (code "52") (name "unconnected-(U1A-SWDIO-Pad35)") (class "Default")
      (node (ref "U1") (pin "35") (pinfunction "SWDIO_35") (pintype "bidirectional+no_connect"))
    )
  )
)
